# nonregulation-level-shifter-mk-2_2.net
KiCad netlist of a schematic drawn in EAGLE
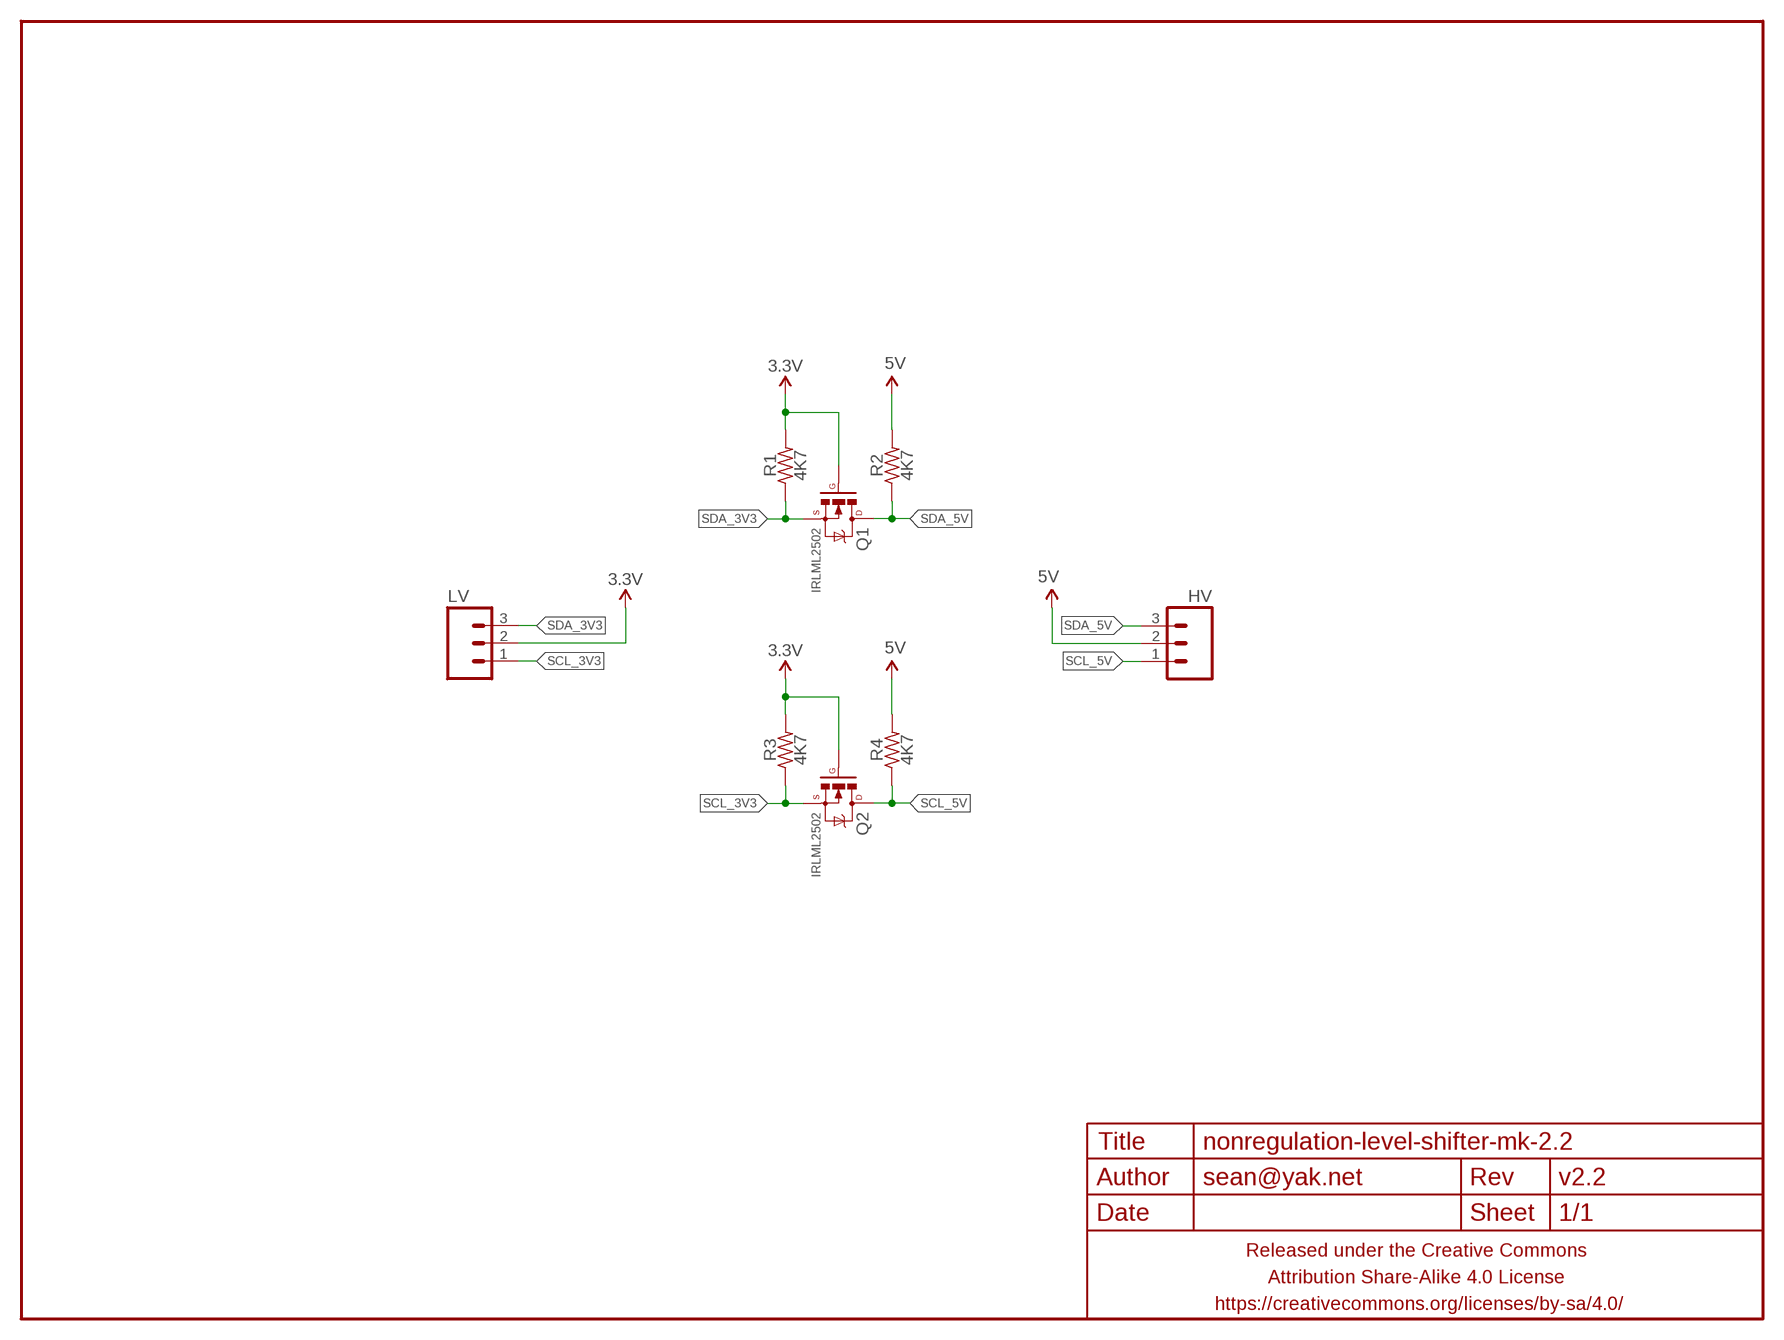
[diagram p0: schematic, sheet 1]

(export (version "E")
  (design (tool "Eeschema 10.0.6"))
  (components
    (comp (ref "FRAME1")
      (value "FRAME-LETTERNO_PACKAGE")
      (footprint "eagle-import:DUMMY")
      (fields (field (name "DESIGNER") "sean@yak.net") (field (name "VERSION") "v2.2"))
      (libsource (lib "eagle-import") (part "FRAME-LETTERNO_PACKAGE"))
    )
    (comp (ref "HV")
      (value "M03PTH-CENTERED")
      (footprint "eagle-import:1X03-CENTERED")
      (libsource (lib "eagle-import") (part "M03PTH-CENTERED"))
    )
    (comp (ref "LV")
      (value "M03PTH-CENTERED")
      (footprint "eagle-import:1X03-CENTERED")
      (libsource (lib "eagle-import") (part "M03PTH-CENTERED"))
    )
    (comp (ref "Q1")
      (value "IRLML2502")
      (footprint "eagle-import:SOT23")
      (libsource (lib "eagle-import") (part "MOSFET-NCHANNELIRLML2502"))
    )
    (comp (ref "Q2")
      (value "IRLML2502")
      (footprint "eagle-import:SOT23")
      (libsource (lib "eagle-import") (part "MOSFET-NCHANNELIRLML2502"))
    )
    (comp (ref "R1")
      (value "4K7")
      (footprint "eagle-import:R0603")
      (libsource (lib "eagle-import") (part "RESISTORR0603"))
    )
    (comp (ref "R2")
      (value "4K7")
      (footprint "eagle-import:R0603")
      (libsource (lib "eagle-import") (part "RESISTORR0603"))
    )
    (comp (ref "R3")
      (value "4K7")
      (footprint "eagle-import:R0603")
      (libsource (lib "eagle-import") (part "RESISTORR0603"))
    )
    (comp (ref "R4")
      (value "4K7")
      (footprint "eagle-import:R0603")
      (libsource (lib "eagle-import") (part "RESISTORR0603"))
    )
  )
  (nets
    (net (code "1") (name "3.3V") (class "Default")
      (node (ref "LV") (pin "2") (pinfunction "2_2") (pintype "passive"))
      (node (ref "Q1") (pin "1") (pinfunction "G_1") (pintype "passive"))
      (node (ref "Q2") (pin "1") (pinfunction "G_1") (pintype "passive"))
      (node (ref "R1") (pin "2") (pinfunction "2_2") (pintype "passive"))
      (node (ref "R3") (pin "2") (pinfunction "2_2") (pintype "passive"))
    )
    (net (code "2") (name "5V") (class "Default")
      (node (ref "HV") (pin "2") (pinfunction "2_2") (pintype "passive"))
      (node (ref "R2") (pin "2") (pinfunction "2_2") (pintype "passive"))
      (node (ref "R4") (pin "2") (pinfunction "2_2") (pintype "passive"))
    )
    (net (code "3") (name "SCL_3V3") (class "Default")
      (node (ref "LV") (pin "1") (pinfunction "1_1") (pintype "passive"))
      (node (ref "Q2") (pin "2") (pinfunction "S_2") (pintype "passive"))
      (node (ref "R3") (pin "1") (pinfunction "1_1") (pintype "passive"))
    )
    (net (code "4") (name "SCL_5V") (class "Default")
      (node (ref "HV") (pin "1") (pinfunction "1_1") (pintype "passive"))
      (node (ref "Q2") (pin "3") (pinfunction "D_3") (pintype "passive"))
      (node (ref "R4") (pin "1") (pinfunction "1_1") (pintype "passive"))
    )
    (net (code "5") (name "SDA_3V3") (class "Default")
      (node (ref "LV") (pin "3") (pinfunction "3_3") (pintype "passive"))
      (node (ref "Q1") (pin "2") (pinfunction "S_2") (pintype "passive"))
      (node (ref "R1") (pin "1") (pinfunction "1_1") (pintype "passive"))
    )
    (net (code "6") (name "SDA_5V") (class "Default")
      (node (ref "HV") (pin "3") (pinfunction "3_3") (pintype "passive"))
      (node (ref "Q1") (pin "3") (pinfunction "D_3") (pintype "passive"))
      (node (ref "R2") (pin "1") (pinfunction "1_1") (pintype "passive"))
    )
  )
)
